# Rat.net
KiCad netlist of a schematic drawn in Altium Designer
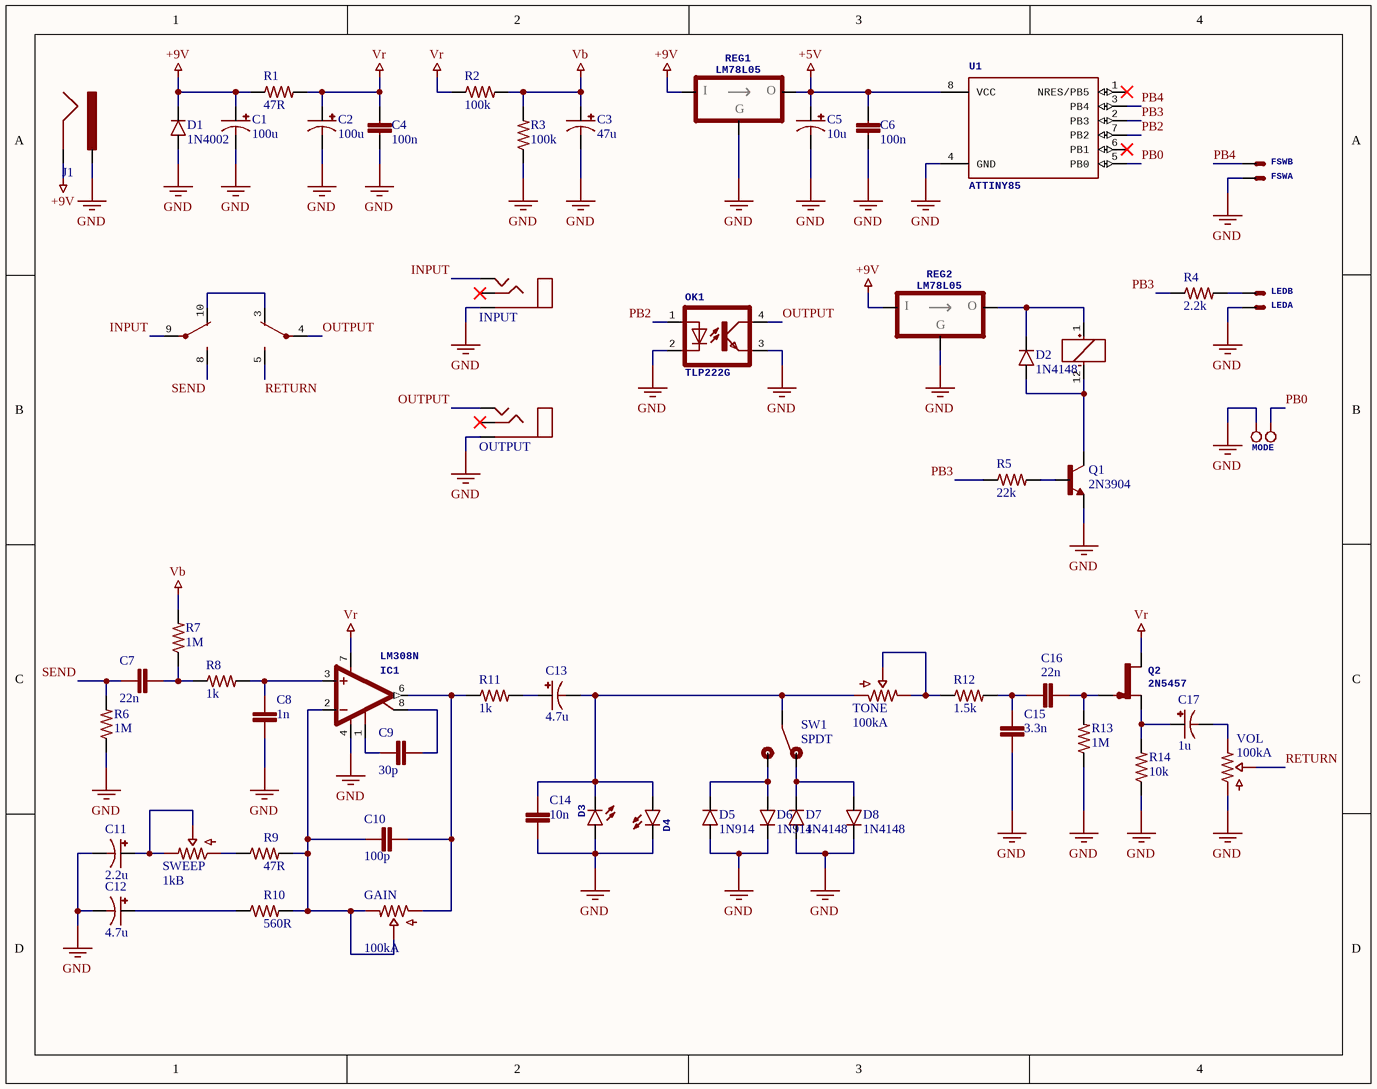
[diagram p0: Rat.SchDoc]

(export (version "E")
  (design (tool "Eeschema 10.0.6"))
  (components
    (comp (ref "C1")
      (value "100u")
      (footprint "ELEC_050_020")
      (description "100u 16V electrolytic capacitor")
      (libsource (lib "Pedals") (part "ELEC_100u_16V"))
    )
    (comp (ref "C2")
      (value "100u")
      (footprint "ELEC_050_020")
      (description "100u 16V electrolytic capacitor")
      (libsource (lib "Pedals") (part "ELEC_100u_16V"))
    )
    (comp (ref "C3")
      (value "47u")
      (footprint "ELEC_050_020")
      (description "47u 25V electrolytic capacitor")
      (libsource (lib "Pedals") (part "ELEC_47u_25V"))
    )
    (comp (ref "C4")
      (value "100n")
      (footprint "CER_050")
      (description "100n MLCC X7R radial capacitor")
      (libsource (lib "") (part "CER_100n_1"))
    )
    (comp (ref "C5")
      (value "10u")
      (footprint "ELEC_040_020")
      (description "10u 50V electrolytic capacitor")
      (libsource (lib "Pedals") (part "ELEC_10u_50V"))
    )
    (comp (ref "C6")
      (value "100n")
      (footprint "CER_050")
      (description "100n MLCC X7R radial capacitor")
      (libsource (lib "Pedals") (part "CER_100n"))
    )
    (comp (ref "C7")
      (value "22n")
      (footprint "FILMBOX_SMALL")
      (description "22n 100V polyester film box capacitor")
      (libsource (lib "Pedals") (part "FILMBOX_22n"))
    )
    (comp (ref "C8")
      (value "1n")
      (footprint "FILMBOX_SMALL")
      (description "1n 100V polyester film box capacitor")
      (libsource (lib "Pedals") (part "FILMBOX_1n"))
    )
    (comp (ref "C9")
      (value "30p")
      (footprint "CER_050")
      (description "30p MLCC X7R radial capacitor")
      (libsource (lib "Pedals") (part "CER_30p"))
    )
    (comp (ref "C10")
      (value "100p")
      (footprint "CER_050")
      (description "100p MLCC X7R radial capacitor")
      (libsource (lib "Pedals") (part "CER_100p"))
    )
    (comp (ref "C11")
      (value "2.2u")
      (footprint "ELEC_LESR_050_020")
      (description "2.2u 50V Low ESR ectrolytic capacitor")
      (libsource (lib "Pedals") (part "ELEC_LESR_2.2u_50V"))
    )
    (comp (ref "C12")
      (value "4.7u")
      (footprint "ELEC_LESR_050_020")
      (description "4.7u 50V Low ESR ectrolytic capacitor")
      (libsource (lib "") (part "ELEC_LESR_4.7u_50V_1"))
    )
    (comp (ref "C13")
      (value "4.7u")
      (footprint "ELEC_LESR_050_020")
      (description "4.7u 50V Low ESR ectrolytic capacitor")
      (libsource (lib "Pedals") (part "ELEC_LESR_4.7u_50V"))
    )
    (comp (ref "C14")
      (value "10n")
      (footprint "FILMBOX_SMALL")
      (description "10n 100V polyester film box capacitor")
      (libsource (lib "Pedals") (part "FILMBOX_10n"))
    )
    (comp (ref "C15")
      (value "3.3n")
      (footprint "FILMBOX_SMALL")
      (description "3.3n 100V polyester film box capacitor")
      (libsource (lib "Pedals") (part "FILMBOX_3.3n"))
    )
    (comp (ref "C16")
      (value "22n")
      (footprint "FILMBOX_SMALL")
      (description "22n 100V polyester film box capacitor")
      (libsource (lib "Pedals") (part "FILMBOX_22n"))
    )
    (comp (ref "C17")
      (value "1u")
      (footprint "ELEC_LESR_040_020")
      (description "1u 50V Low ESR electrolytic capacitor")
      (libsource (lib "Pedals") (part "ELEC_LESR_1u_50V"))
    )
    (comp (ref "D1") (value "1N4002") (footprint "DO41_2") (libsource (lib "Pedals") (part "1N4002")))
    (comp (ref "D2") (value "1N4148") (footprint "DO35_2") (libsource (lib "Pedals") (part "1N4148")))
    (comp (ref "D3")
      (value "LED")
      (footprint "LED_3MM")
      (description "3mm LED")
      (libsource (lib "Pedals") (part "LED"))
    )
    (comp (ref "D4")
      (value "LED")
      (footprint "LED_3MM")
      (description "3mm LED")
      (libsource (lib "Pedals") (part "LED"))
    )
    (comp (ref "D5") (value "1N914") (footprint "DO35_3") (libsource (lib "Pedals") (part "1N914")))
    (comp (ref "D6") (value "1N914") (footprint "DO35_3") (libsource (lib "Pedals") (part "1N914")))
    (comp (ref "D7") (value "1N4148") (footprint "DO35_2") (libsource (lib "Pedals") (part "1N4148")))
    (comp (ref "D8") (value "1N4148") (footprint "DO35_2") (libsource (lib "Pedals") (part "1N4148")))
    (comp (ref "FSW")
      (value "JST-XH-02")
      (footprint "JST-XH-02")
      (description "2 Pins male XH header")
      (libsource (lib "Pedals") (part "JST-XH-02"))
    )
    (comp (ref "GAIN")
      (value "100kA")
      (footprint "ALPHA_16mm_BOTTOM")
      (description "100k Log potentiometer round shaft")
      (libsource (lib "Pedals") (part "100kA_ALPHA_16mm"))
    )
    (comp (ref "IC1") (value "LM308N") (footprint "DIL8") (libsource (lib "Pedals") (part "LM308N")))
    (comp (ref "INPUT")
      (value "STEREO")
      (footprint "STEREO")
      (description "6.35mm stereo insulated socket jack PCB mounted")
      (libsource (lib "Pedals") (part "STEREO"))
    )
    (comp (ref "J1")
      (value "DC_JACK")
      (footprint "DC_JACK")
      (description "DC Power jack 2.1mm barrel")
      (libsource (lib "Pedals") (part "DC_JACK"))
    )
    (comp (ref "K1") (value "NA5W-K") (footprint "NA5") (libsource (lib "") (part "NA5W-K_1")))
    (comp (ref "LED")
      (value "JST-XH-02")
      (footprint "JST-XH-02")
      (description "2 Pins male XH header")
      (libsource (lib "Pedals") (part "JST-XH-02"))
    )
    (comp (ref "MODE")
      (value "HEADER_2PINS")
      (footprint "HEADER_2PINS")
      (description "2 Pins male header")
      (libsource (lib "Pedals") (part "HEADER_2PINS"))
    )
    (comp (ref "OK1") (value "TLP222G") (footprint "DIL4") (libsource (lib "Pedals") (part "TLP222G")))
    (comp (ref "OUTPUT")
      (value "STEREO")
      (footprint "STEREO")
      (description "6.35mm stereo insulated socket jack PCB mounted")
      (libsource (lib "Pedals") (part "STEREO"))
    )
    (comp (ref "Q1") (value "2N3904") (footprint "TO92") (libsource (lib "Pedals") (part "2N3904")))
    (comp (ref "Q2") (value "2N5457") (footprint "TO92") (libsource (lib "Pedals") (part "2N5457")))
    (comp (ref "R1")
      (value "47R")
      (footprint "R_3_47R_025W")
      (description "47R metal film 1/4W Resistor")
      (libsource (lib "Pedals") (part "R_3_47R_025W"))
    )
    (comp (ref "R2")
      (value "100k")
      (footprint "R_3_100k_025W")
      (description "100k metal film 1/4W Resistor")
      (libsource (lib "Pedals") (part "R_3_100k_025W"))
    )
    (comp (ref "R3")
      (value "100k")
      (footprint "R_3_100k_025W")
      (description "100k metal film 1/4W Resistor")
      (libsource (lib "Pedals") (part "R_3_100k_025W"))
    )
    (comp (ref "R4")
      (value "2.2k")
      (footprint "R_3_2,2k_025W")
      (description "2.2k metal film 1/4W Resistor")
      (libsource (lib "Pedals") (part "R_3_2.2k_025W"))
    )
    (comp (ref "R5")
      (value "22k")
      (footprint "R_3_22k_025W")
      (description "22k metal film 1/4W Resistor")
      (libsource (lib "Pedals") (part "R_3_22k_025W"))
    )
    (comp (ref "R6")
      (value "1M")
      (footprint "R_3_1M_025W")
      (description "1M metal film 1/4W Resistor")
      (libsource (lib "Pedals") (part "R_3_1M_025W"))
    )
    (comp (ref "R7")
      (value "1M")
      (footprint "R_3_1M_025W")
      (description "1M metal film 1/4W Resistor")
      (libsource (lib "Pedals") (part "R_3_1M_025W"))
    )
    (comp (ref "R8")
      (value "1k")
      (footprint "R_3_1k_025W")
      (description "1k metal film 1/4W Resistor")
      (libsource (lib "Pedals") (part "R_3_1k_025W"))
    )
    (comp (ref "R9")
      (value "47R")
      (footprint "R_3_47R_025W")
      (description "47R metal film 1/4W Resistor")
      (libsource (lib "Pedals") (part "R_3_47R_025W"))
    )
    (comp (ref "R10")
      (value "560R")
      (footprint "R_3_560R_025W")
      (description "560R metal film 1/4W Resistor")
      (libsource (lib "Pedals") (part "R_3_560R_025W"))
    )
    (comp (ref "R11")
      (value "1k")
      (footprint "R_3_1k_025W")
      (description "1k metal film 1/4W Resistor")
      (libsource (lib "Pedals") (part "R_3_1k_025W"))
    )
    (comp (ref "R12")
      (value "1.5k")
      (footprint "R_3_1.5k_025W")
      (description "1.5k metal film 1/4W Resistor")
      (libsource (lib "Pedals") (part "R_3_1.5k_025W"))
    )
    (comp (ref "R13")
      (value "1M")
      (footprint "R_3_1M_025W")
      (description "1M metal film 1/4W Resistor")
      (libsource (lib "Pedals") (part "R_3_1M_025W"))
    )
    (comp (ref "R14")
      (value "10k")
      (footprint "R_3_10k_025W")
      (description "10k metal film 1/4W Resistor")
      (libsource (lib "Pedals") (part "R_3_10k_025W"))
    )
    (comp (ref "REG1")
      (value "LM78L05")
      (footprint "TO92")
      (description "78L05")
      (libsource (lib "Pedals") (part "LM78L05"))
    )
    (comp (ref "REG2")
      (value "LM78L05")
      (footprint "TO92")
      (description "78L05")
      (libsource (lib "Pedals") (part "LM78L05"))
    )
    (comp (ref "SW1")
      (value "SPDT")
      (footprint "SPDT")
      (description "SPDT toggle switch ON/OFF/ON")
      (libsource (lib "Pedals") (part "SPDT_ON-OFF-ON"))
    )
    (comp (ref "SWEEP")
      (value "1kB")
      (footprint "ALPHA_16mm_BOTTOM")
      (description "1k Lin potentiometer round shaft")
      (libsource (lib "Pedals") (part "1kB_ALPHA_16mm"))
    )
    (comp (ref "TONE")
      (value "100kA")
      (footprint "ALPHA_16mm_BOTTOM")
      (description "100k Log potentiometer round shaft")
      (libsource (lib "Pedals") (part "100kA_ALPHA_16mm"))
    )
    (comp (ref "U1")
      (value "ATTINY85")
      (footprint "DIP8")
      (description "ATTINY85-20PU")
      (libsource (lib "Pedals") (part "ATTINY85"))
    )
    (comp (ref "VOL")
      (value "100kA")
      (footprint "ALPHA_16mm_BOTTOM")
      (description "100k Log potentiometer round shaft")
      (libsource (lib "Pedals") (part "100kA_ALPHA_16mm"))
    )
  )
  (nets
    (net (code "1") (name "+5V") (class "Default")
      (node (ref "C5") (pin "+") (pinfunction "+_+") (pintype "passive"))
      (node (ref "C6") (pin "2") (pinfunction "2_2") (pintype "passive"))
      (node (ref "REG1") (pin "3") (pinfunction "VO_3") (pintype "power_in"))
      (node (ref "U1") (pin "8") (pinfunction "VCC_8") (pintype "power_in"))
    )
    (net (code "2") (name "+9V") (class "Default")
      (node (ref "C1") (pin "+") (pinfunction "+_+") (pintype "passive"))
      (node (ref "D1") (pin "C") (pinfunction "C_C") (pintype "passive"))
      (node (ref "J1") (pin "GND") (pinfunction "GND_GND") (pintype "passive"))
      (node (ref "R1") (pin "1") (pinfunction "1_1") (pintype "passive"))
      (node (ref "REG1") (pin "1") (pinfunction "VI_1") (pintype "power_in"))
      (node (ref "REG2") (pin "1") (pinfunction "VI_1") (pintype "power_in"))
    )
    (net (code "3") (name "/INPUT") (class "Default")
      (node (ref "INPUT") (pin "T") (pinfunction "T_T") (pintype "passive"))
      (node (ref "K1") (pin "9") (pinfunction "P_9") (pintype "passive"))
    )
    (net (code "4") (name "/OUTPUT") (class "Default")
      (node (ref "K1") (pin "4") (pinfunction "P_4") (pintype "passive"))
      (node (ref "OK1") (pin "4") (pinfunction "COL_4") (pintype "passive"))
      (node (ref "OUTPUT") (pin "T") (pinfunction "T_T") (pintype "passive"))
    )
    (net (code "5") (name "/PB0") (class "Default")
      (node (ref "MODE") (pin "2") (pinfunction "2_2") (pintype "passive"))
      (node (ref "U1") (pin "5") (pinfunction "PB0_5") (pintype "bidirectional"))
    )
    (net (code "6") (name "/PB2") (class "Default")
      (node (ref "OK1") (pin "1") (pinfunction "A_1") (pintype "passive"))
      (node (ref "U1") (pin "7") (pinfunction "PB2_7") (pintype "bidirectional"))
    )
    (net (code "7") (name "/PB3") (class "Default")
      (node (ref "R4") (pin "1") (pinfunction "1_1") (pintype "passive"))
      (node (ref "R5") (pin "1") (pinfunction "1_1") (pintype "passive"))
      (node (ref "U1") (pin "2") (pinfunction "PB3_2") (pintype "bidirectional"))
    )
    (net (code "8") (name "/PB4") (class "Default")
      (node (ref "FSW") (pin "1") (pinfunction "S_1") (pintype "passive"))
      (node (ref "U1") (pin "3") (pinfunction "PB4_3") (pintype "bidirectional"))
    )
    (net (code "9") (name "/RETURN") (class "Default")
      (node (ref "K1") (pin "5") (pinfunction "S_5") (pintype "passive"))
      (node (ref "VOL") (pin "2") (pinfunction "2_2") (pintype "passive"))
    )
    (net (code "10") (name "/SEND") (class "Default")
      (node (ref "C7") (pin "2") (pinfunction "2_2") (pintype "passive"))
      (node (ref "K1") (pin "8") (pinfunction "S_8") (pintype "passive"))
      (node (ref "R6") (pin "2") (pinfunction "2_2") (pintype "passive"))
    )
    (net (code "11") (name "GND") (class "Default")
      (node (ref "C1") (pin "-") (pinfunction "-_-") (pintype "passive"))
      (node (ref "C11") (pin "-") (pinfunction "-_-") (pintype "passive"))
      (node (ref "C12") (pin "-") (pinfunction "-_-") (pintype "passive"))
      (node (ref "C14") (pin "2") (pinfunction "2_2") (pintype "passive"))
      (node (ref "C15") (pin "2") (pinfunction "2_2") (pintype "passive"))
      (node (ref "C2") (pin "-") (pinfunction "-_-") (pintype "passive"))
      (node (ref "C3") (pin "-") (pinfunction "-_-") (pintype "passive"))
      (node (ref "C4") (pin "2") (pinfunction "2_2") (pintype "passive"))
      (node (ref "C5") (pin "-") (pinfunction "-_-") (pintype "passive"))
      (node (ref "C6") (pin "1") (pinfunction "1_1") (pintype "passive"))
      (node (ref "C8") (pin "2") (pinfunction "2_2") (pintype "passive"))
      (node (ref "D1") (pin "A") (pinfunction "A_A") (pintype "passive"))
      (node (ref "D3") (pin "ANODE") (pinfunction "A_ANODE") (pintype "passive"))
      (node (ref "D4") (pin "P$1") (pinfunction "C_P$1") (pintype "passive"))
      (node (ref "D5") (pin "A") (pinfunction "A_A") (pintype "passive"))
      (node (ref "D6") (pin "C") (pinfunction "C_C") (pintype "passive"))
      (node (ref "D7") (pin "A") (pinfunction "A_A") (pintype "passive"))
      (node (ref "D8") (pin "C") (pinfunction "C_C") (pintype "passive"))
      (node (ref "FSW") (pin "2") (pinfunction "S_2") (pintype "passive"))
      (node (ref "IC1") (pin "4") (pinfunction "V-_4") (pintype "power_in"))
      (node (ref "INPUT") (pin "S") (pinfunction "S_S") (pintype "passive"))
      (node (ref "J1") (pin "PWR") (pinfunction "PWR_PWR") (pintype "passive"))
      (node (ref "LED") (pin "2") (pinfunction "S_2") (pintype "passive"))
      (node (ref "MODE") (pin "1") (pinfunction "1_1") (pintype "passive"))
      (node (ref "OK1") (pin "2") (pinfunction "C_2") (pintype "passive"))
      (node (ref "OK1") (pin "3") (pinfunction "EMIT_3") (pintype "passive"))
      (node (ref "OUTPUT") (pin "S") (pinfunction "S_S") (pintype "passive"))
      (node (ref "Q1") (pin "3") (pinfunction "E_3") (pintype "passive"))
      (node (ref "R13") (pin "1") (pinfunction "1_1") (pintype "passive"))
      (node (ref "R14") (pin "1") (pinfunction "1_1") (pintype "passive"))
      (node (ref "R3") (pin "1") (pinfunction "1_1") (pintype "passive"))
      (node (ref "R6") (pin "1") (pinfunction "1_1") (pintype "passive"))
      (node (ref "REG1") (pin "2") (pinfunction "GND_2") (pintype "power_in"))
      (node (ref "REG2") (pin "2") (pinfunction "GND_2") (pintype "power_in"))
      (node (ref "U1") (pin "4") (pinfunction "GND_4") (pintype "power_in"))
      (node (ref "VOL") (pin "1") (pinfunction "1_1") (pintype "passive"))
    )
    (net (code "12") (name "Net-(C7-Pad1)") (class "Default")
      (node (ref "C7") (pin "1") (pinfunction "1_1") (pintype "passive"))
      (node (ref "R7") (pin "1") (pinfunction "1_1") (pintype "passive"))
      (node (ref "R8") (pin "1") (pinfunction "1_1") (pintype "passive"))
    )
    (net (code "13") (name "Net-(C11-Pad+)") (class "Default")
      (node (ref "C11") (pin "+") (pinfunction "+_+") (pintype "passive"))
      (node (ref "SWEEP") (pin "2") (pinfunction "2_2") (pintype "passive"))
      (node (ref "SWEEP") (pin "3") (pinfunction "3_3") (pintype "passive"))
    )
    (net (code "14") (name "Net-(C12-Pad+)") (class "Default")
      (node (ref "C12") (pin "+") (pinfunction "+_+") (pintype "passive"))
      (node (ref "R10") (pin "1") (pinfunction "1_1") (pintype "passive"))
    )
    (net (code "15") (name "Net-(C13-Pad+)") (class "Default")
      (node (ref "C13") (pin "+") (pinfunction "+_+") (pintype "passive"))
      (node (ref "R11") (pin "2") (pinfunction "2_2") (pintype "passive"))
    )
    (net (code "16") (name "Net-(C15-Pad1)") (class "Default")
      (node (ref "C15") (pin "1") (pinfunction "1_1") (pintype "passive"))
      (node (ref "C16") (pin "2") (pinfunction "2_2") (pintype "passive"))
      (node (ref "R12") (pin "2") (pinfunction "2_2") (pintype "passive"))
    )
    (net (code "17") (name "Net-(C17-Pad-)") (class "Default")
      (node (ref "C17") (pin "-") (pinfunction "-_-") (pintype "passive"))
      (node (ref "VOL") (pin "3") (pinfunction "3_3") (pintype "passive"))
    )
    (net (code "18") (name "Net-(D3-C)") (class "Default")
      (node (ref "C13") (pin "-") (pinfunction "-_-") (pintype "passive"))
      (node (ref "C14") (pin "1") (pinfunction "1_1") (pintype "passive"))
      (node (ref "D3") (pin "P$1") (pinfunction "C_P$1") (pintype "passive"))
      (node (ref "D4") (pin "ANODE") (pinfunction "A_ANODE") (pintype "passive"))
      (node (ref "SW1") (pin "2") (pinfunction "P_2") (pintype "passive"))
      (node (ref "TONE") (pin "1") (pinfunction "1_1") (pintype "passive"))
    )
    (net (code "19") (name "Net-(IC1-+IN)") (class "Default")
      (node (ref "C8") (pin "1") (pinfunction "1_1") (pintype "passive"))
      (node (ref "IC1") (pin "3") (pinfunction "+IN_3") (pintype "passive"))
      (node (ref "R8") (pin "2") (pinfunction "2_2") (pintype "passive"))
    )
    (net (code "20") (name "Net-(IC1--IN)") (class "Default")
      (node (ref "C10") (pin "2") (pinfunction "2_2") (pintype "passive"))
      (node (ref "GAIN") (pin "2") (pinfunction "2_2") (pintype "passive"))
      (node (ref "GAIN") (pin "3") (pinfunction "3_3") (pintype "passive"))
      (node (ref "IC1") (pin "2") (pinfunction "-IN_2") (pintype "passive"))
      (node (ref "R10") (pin "2") (pinfunction "2_2") (pintype "passive"))
      (node (ref "R9") (pin "2") (pinfunction "2_2") (pintype "passive"))
    )
    (net (code "21") (name "Net-(IC1-CMP1)") (class "Default")
      (node (ref "C9") (pin "2") (pinfunction "2_2") (pintype "passive"))
      (node (ref "IC1") (pin "1") (pinfunction "CMP1_1") (pintype "passive"))
    )
    (net (code "22") (name "Net-(IC1-CMP2)") (class "Default")
      (node (ref "C9") (pin "1") (pinfunction "1_1") (pintype "passive"))
      (node (ref "IC1") (pin "8") (pinfunction "CMP2_8") (pintype "passive"))
    )
    (net (code "23") (name "Net-(IC1-OUT)") (class "Default")
      (node (ref "C10") (pin "1") (pinfunction "1_1") (pintype "passive"))
      (node (ref "GAIN") (pin "1") (pinfunction "1_1") (pintype "passive"))
      (node (ref "IC1") (pin "6") (pinfunction "OUT_6") (pintype "output"))
      (node (ref "R11") (pin "1") (pinfunction "1_1") (pintype "passive"))
    )
    (net (code "24") (name "Net-(K1A-+)") (class "Default")
      (node (ref "D2") (pin "C") (pinfunction "C_C") (pintype "passive"))
      (node (ref "K1") (pin "1") (pinfunction "+_1") (pintype "passive"))
      (node (ref "REG2") (pin "3") (pinfunction "VO_3") (pintype "power_in"))
    )
    (net (code "25") (name "Net-(K1A--)") (class "Default")
      (node (ref "D2") (pin "A") (pinfunction "A_A") (pintype "passive"))
      (node (ref "K1") (pin "12") (pinfunction "-_12") (pintype "passive"))
      (node (ref "Q1") (pin "1") (pinfunction "C_1") (pintype "passive"))
    )
    (net (code "26") (name "Net-(K1B-O)") (class "Default")
      (node (ref "K1") (pin "10") (pinfunction "O_10") (pintype "passive"))
      (node (ref "K1") (pin "3") (pinfunction "O_3") (pintype "passive"))
    )
    (net (code "27") (name "Net-(LEDB-S)") (class "Default")
      (node (ref "LED") (pin "1") (pinfunction "S_1") (pintype "passive"))
      (node (ref "R4") (pin "2") (pinfunction "2_2") (pintype "passive"))
    )
    (net (code "28") (name "Net-(Q1-B)") (class "Default")
      (node (ref "Q1") (pin "2") (pinfunction "B_2") (pintype "passive"))
      (node (ref "R5") (pin "2") (pinfunction "2_2") (pintype "passive"))
    )
    (net (code "29") (name "Net-(Q2-G)") (class "Default")
      (node (ref "C16") (pin "1") (pinfunction "1_1") (pintype "passive"))
      (node (ref "Q2") (pin "1") (pinfunction "G_1") (pintype "passive"))
      (node (ref "R13") (pin "2") (pinfunction "2_2") (pintype "passive"))
    )
    (net (code "30") (name "Net-(Q2-S)") (class "Default")
      (node (ref "C17") (pin "+") (pinfunction "+_+") (pintype "passive"))
      (node (ref "Q2") (pin "2") (pinfunction "S_2") (pintype "passive"))
      (node (ref "R14") (pin "2") (pinfunction "2_2") (pintype "passive"))
    )
    (net (code "31") (name "Net-(R9-Pad1)") (class "Default")
      (node (ref "R9") (pin "1") (pinfunction "1_1") (pintype "passive"))
      (node (ref "SWEEP") (pin "1") (pinfunction "1_1") (pintype "passive"))
    )
    (net (code "32") (name "Net-(R12-Pad1)") (class "Default")
      (node (ref "R12") (pin "1") (pinfunction "1_1") (pintype "passive"))
      (node (ref "TONE") (pin "2") (pinfunction "2_2") (pintype "passive"))
      (node (ref "TONE") (pin "3") (pinfunction "3_3") (pintype "passive"))
    )
    (net (code "33") (name "Net-(SW1-O)") (class "Default")
      (node (ref "D7") (pin "C") (pinfunction "C_C") (pintype "passive"))
      (node (ref "D8") (pin "A") (pinfunction "A_A") (pintype "passive"))
      (node (ref "SW1") (pin "1") (pinfunction "O_1") (pintype "passive"))
    )
    (net (code "34") (name "Net-(SW1-S)") (class "Default")
      (node (ref "D5") (pin "C") (pinfunction "C_C") (pintype "passive"))
      (node (ref "D6") (pin "A") (pinfunction "A_A") (pintype "passive"))
      (node (ref "SW1") (pin "3") (pinfunction "S_3") (pintype "passive"))
    )
    (net (code "35") (name "Vb") (class "Default")
      (node (ref "C3") (pin "+") (pinfunction "+_+") (pintype "passive"))
      (node (ref "R2") (pin "2") (pinfunction "2_2") (pintype "passive"))
      (node (ref "R3") (pin "2") (pinfunction "2_2") (pintype "passive"))
      (node (ref "R7") (pin "2") (pinfunction "2_2") (pintype "passive"))
    )
    (net (code "36") (name "Vr") (class "Default")
      (node (ref "C2") (pin "+") (pinfunction "+_+") (pintype "passive"))
      (node (ref "C4") (pin "1") (pinfunction "1_1") (pintype "passive"))
      (node (ref "IC1") (pin "7") (pinfunction "V+_7") (pintype "power_in"))
      (node (ref "Q2") (pin "3") (pinfunction "D_3") (pintype "passive"))
      (node (ref "R1") (pin "2") (pinfunction "2_2") (pintype "passive"))
      (node (ref "R2") (pin "1") (pinfunction "1_1") (pintype "passive"))
    )
    (net (code "37") (name "unconnected-(INPUT-PadR)") (class "Default")
      (node (ref "INPUT") (pin "R") (pinfunction "R_R") (pintype "passive+no_connect"))
    )
    (net (code "38") (name "unconnected-(OUTPUT-PadR)") (class "Default")
      (node (ref "OUTPUT") (pin "R") (pinfunction "R_R") (pintype "passive+no_connect"))
    )
    (net (code "39") (name "unconnected-(U1-NRES{slash}PB5-Pad1)") (class "Default")
      (node (ref "U1") (pin "1") (pinfunction "NRES/PB5_1") (pintype "bidirectional+no_connect"))
    )
    (net (code "40") (name "unconnected-(U1-PB1-Pad6)") (class "Default")
      (node (ref "U1") (pin "6") (pinfunction "PB1_6") (pintype "bidirectional+no_connect"))
    )
  )
)
